# SCH_Primaluce-Senso-pcb_2024-02-22.net
KiCad netlist of a schematic drawn in EasyEDA
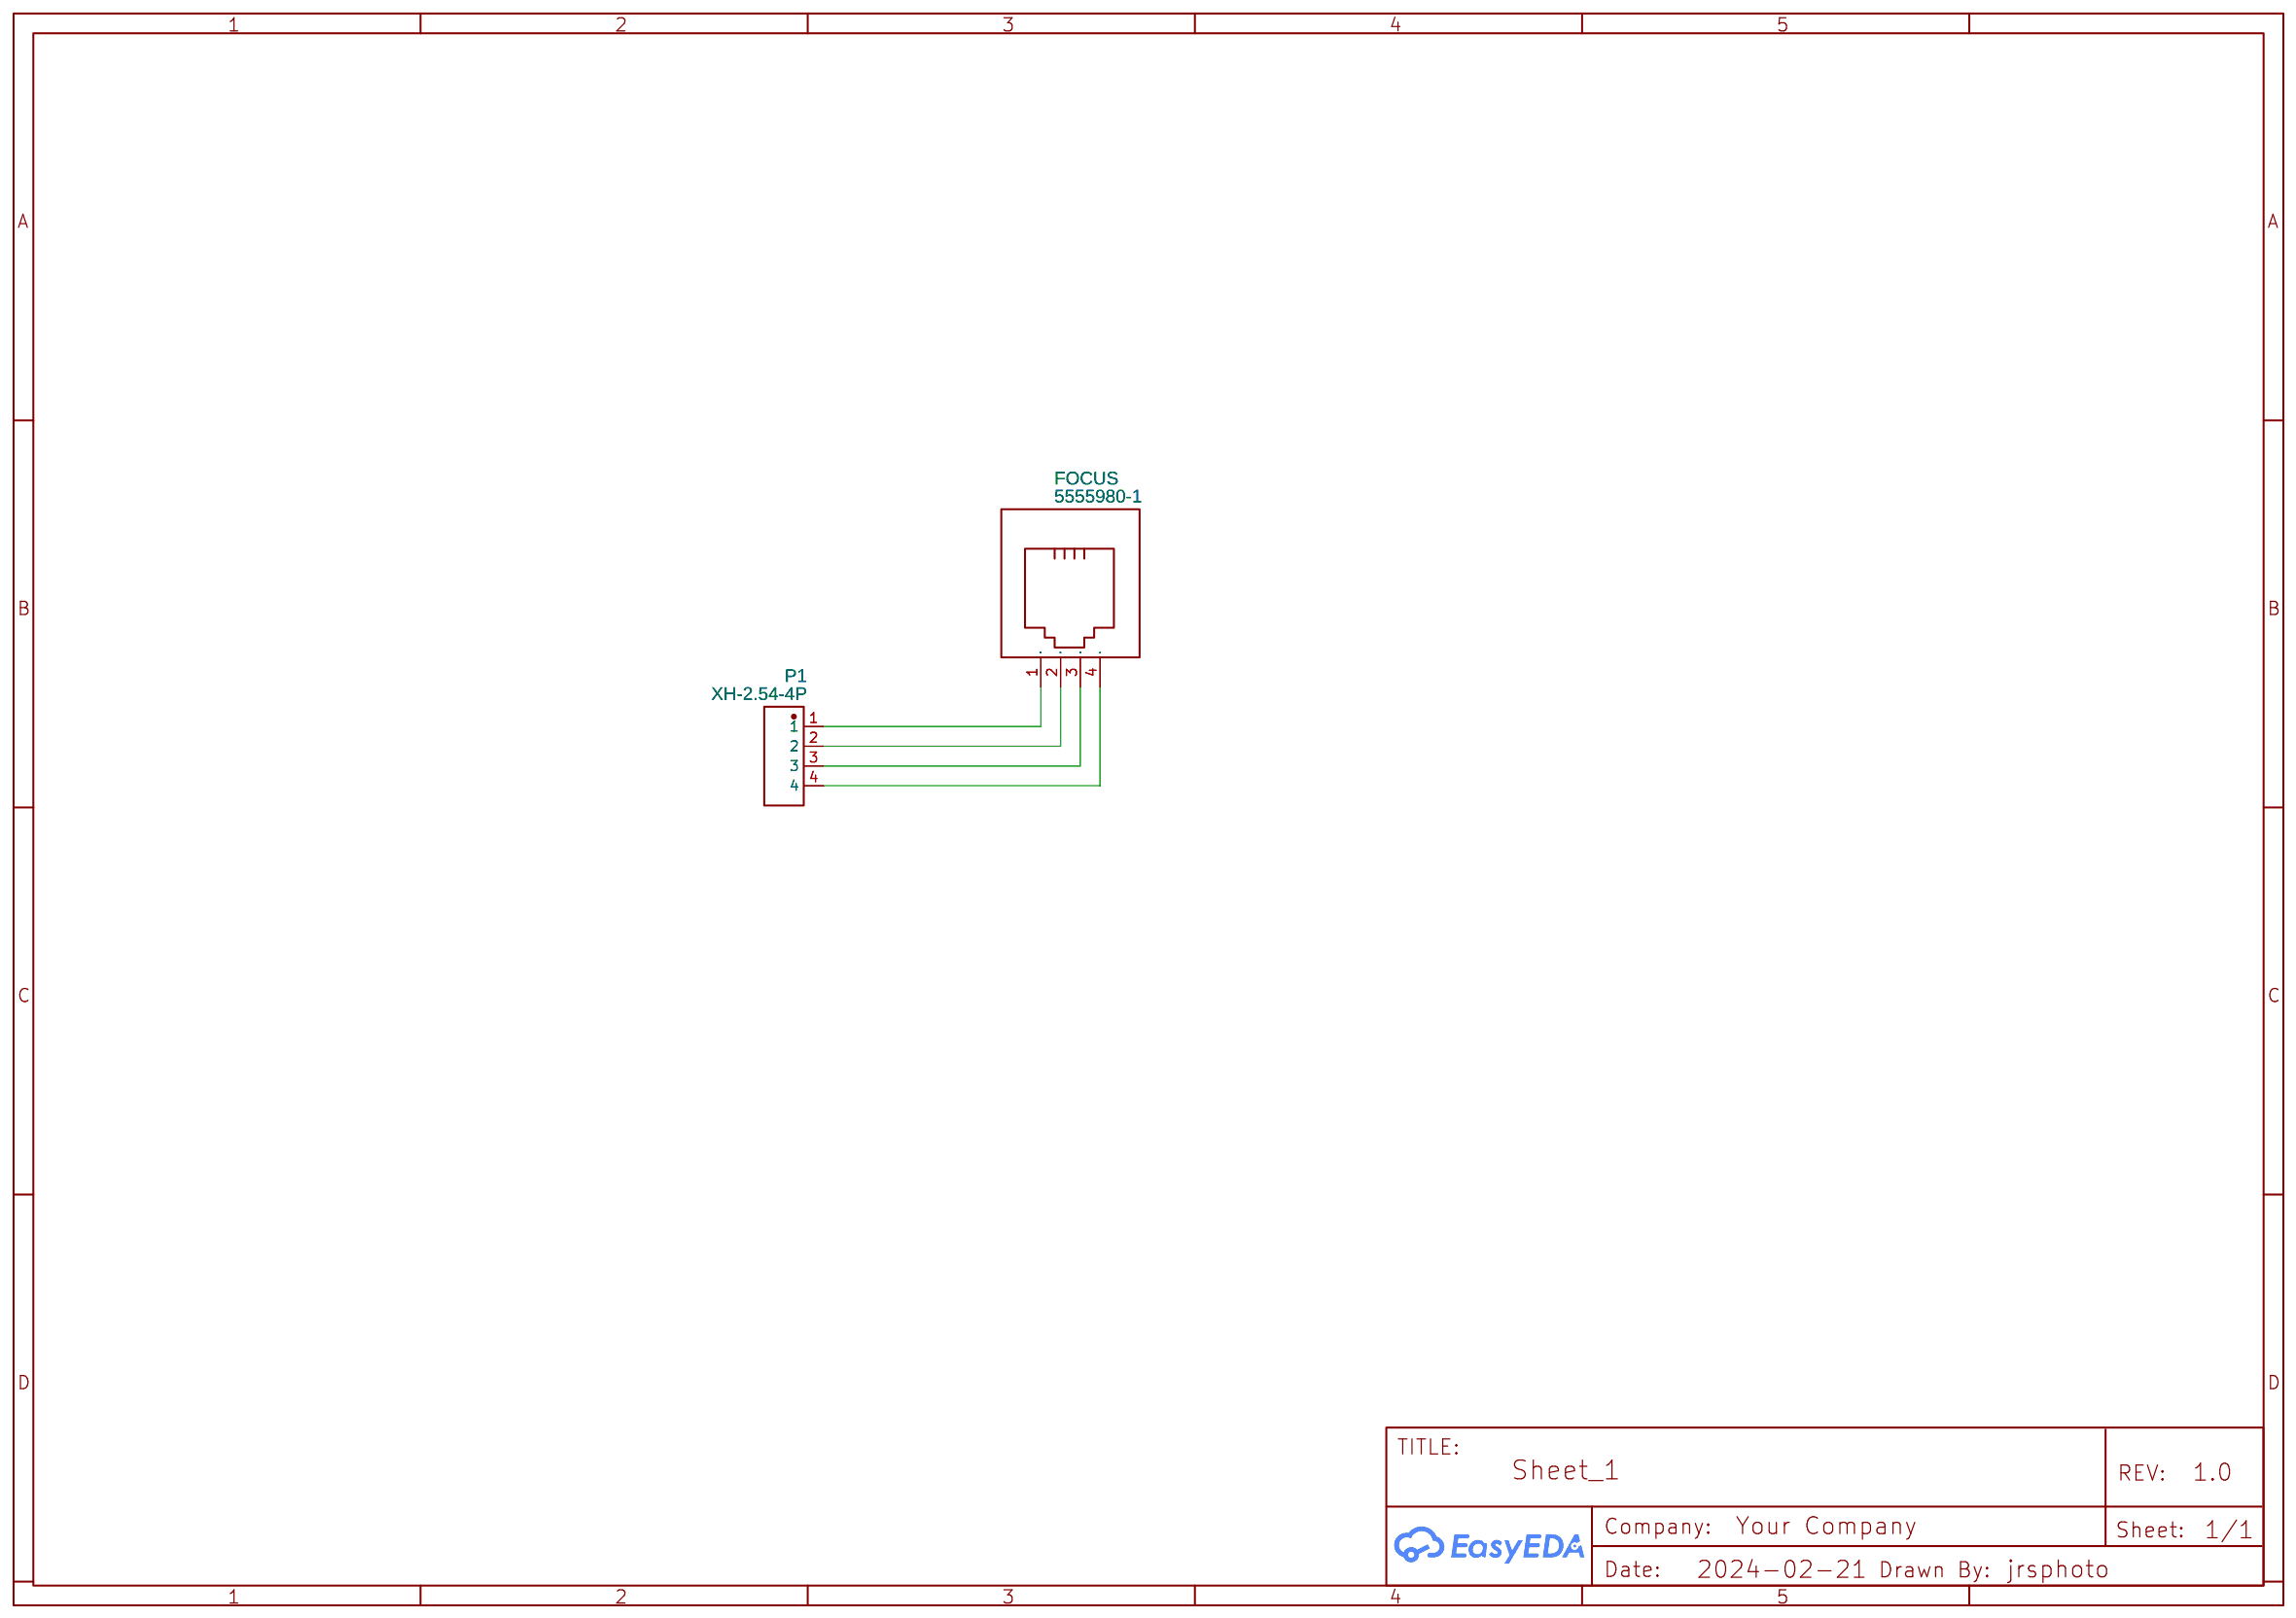
[diagram p0: schematic sheet]

(export (version "E")
  (design (tool "Eeschema 10.0.6"))
  (components
    (comp (ref "FOCUS")
      (value "5555980-1")
      (fields (field (name "Manufacturer") "TE"))
      (libsource (lib "") (part "5555980-1"))
    )
    (comp (ref "P1") (value "XH-2.54-4P") (libsource (lib "") (part "XH-2.54-4P")))
  )
  (nets
    (net (code "1") (name "Net-(FOCUS-Pad1)") (class "Default")
      (node (ref "FOCUS") (pin "1") (pinfunction "1_1") (pintype "unspecified"))
      (node (ref "P1") (pin "1") (pinfunction "1_1") (pintype "unspecified"))
    )
    (net (code "2") (name "Net-(FOCUS-Pad2)") (class "Default")
      (node (ref "FOCUS") (pin "2") (pinfunction "2_2") (pintype "unspecified"))
      (node (ref "P1") (pin "2") (pinfunction "2_2") (pintype "unspecified"))
    )
    (net (code "3") (name "Net-(FOCUS-Pad3)") (class "Default")
      (node (ref "FOCUS") (pin "3") (pinfunction "3_3") (pintype "unspecified"))
      (node (ref "P1") (pin "3") (pinfunction "3_3") (pintype "unspecified"))
    )
    (net (code "4") (name "Net-(FOCUS-Pad4)") (class "Default")
      (node (ref "FOCUS") (pin "4") (pinfunction "4_4") (pintype "unspecified"))
      (node (ref "P1") (pin "4") (pinfunction "4_4") (pintype "unspecified"))
    )
  )
)
